# DAC_Schematic.net
KiCad netlist of a schematic drawn in Altium Designer
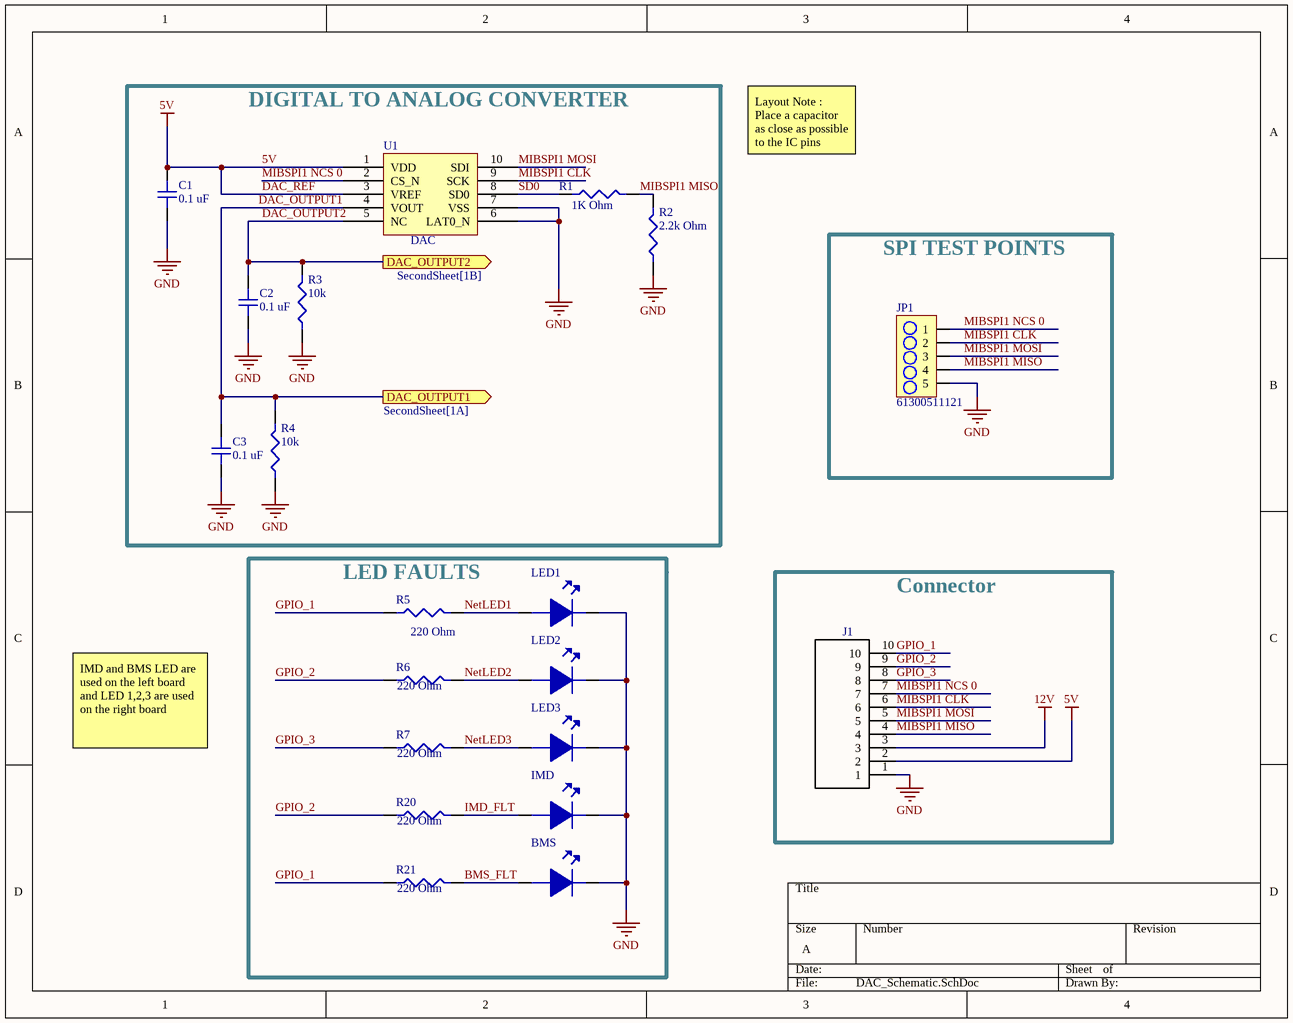
[diagram p0: DAC_Schematic.SchDoc]

(export (version "E")
  (design (tool "Eeschema 10.0.6"))
  (components
    (comp (ref "BMS")
      (value "C503B-RAN-CZ0C0AA1")
      (footprint "Diode")
      (description "LED Uni-Color Red 2-Pin T-1 3/4 Cardboard")
      (fields (field (name "MANUFACTURER") "Cree"))
      (libsource (lib "Dash_Schematic") (part "C503B-RAN-CZ0C0AA1"))
    )
    (comp (ref "C1")
      (value "0.1 uF")
      (footprint "CAPC1608X09N")
      (fields
        (field (name "MANUFACTURER") "KEMET")
        (field (name "MANUFACTURER PART NUMBER") "C0603C104Z3VACTU")
        (field (name "TOLERANCE") "80%")
      )
      (libsource (lib "Dash_Schematic") (part "C0603C104Z3VACTU"))
    )
    (comp (ref "C2")
      (value "0.1 uF")
      (footprint "CAPC1608X09N")
      (fields
        (field (name "MANUFACTURER") "KEMET")
        (field (name "MANUFACTURER PART NUMBER") "C0603C104Z3VACTU")
        (field (name "TOLERANCE") "80%")
      )
      (libsource (lib "Dash_Schematic") (part "C0603C104Z3VACTU"))
    )
    (comp (ref "C3")
      (value "0.1 uF")
      (footprint "CAPC1608X09N")
      (fields
        (field (name "MANUFACTURER") "KEMET")
        (field (name "MANUFACTURER PART NUMBER") "C0603C104Z3VACTU")
        (field (name "TOLERANCE") "80%")
      )
      (libsource (lib "Dash_Schematic") (part "C0603C104Z3VACTU"))
    )
    (comp (ref "IMD")
      (value "C503B-RAN-CZ0C0AA1")
      (footprint "Diode")
      (description "LED Uni-Color Red 2-Pin T-1 3/4 Cardboard")
      (fields (field (name "MANUFACTURER") "Cree"))
      (libsource (lib "Dash_Schematic") (part "C503B-RAN-CZ0C0AA1"))
    )
    (comp (ref "J1")
      (value "103635-9")
      (footprint "*TE_103635-9")
      (description "10 MTE HDR SRRA LATCH .100CL")
      (fields (field (name "DIGI-KEY_PART_NUMBER") "A28643-ND") (field (name "MF") "TE Connectivity"))
      (libsource (lib "103635-9") (part "103635-9"))
    )
    (comp (ref "JP1")
      (value "61300511121")
      (footprint "5PIN_HEADER")
      (fields (field (name "MANUFACTURER") "Wurth Electronics"))
      (libsource (lib "Dash_Schematic") (part "61300511121"))
    )
    (comp (ref "LED1")
      (value "C503B-RAN-CZ0C0AA1")
      (footprint "Diode")
      (description "LED Uni-Color Red 2-Pin T-1 3/4 Cardboard")
      (fields (field (name "MANUFACTURER") "Cree"))
      (libsource (lib "Dash_Schematic") (part "C503B-RAN-CZ0C0AA1"))
    )
    (comp (ref "LED2")
      (value "C503B-RAN-CZ0C0AA1")
      (footprint "Diode")
      (description "LED Uni-Color Red 2-Pin T-1 3/4 Cardboard")
      (fields (field (name "MANUFACTURER") "Cree"))
      (libsource (lib "Dash_Schematic") (part "C503B-RAN-CZ0C0AA1"))
    )
    (comp (ref "LED3")
      (value "C503B-RAN-CZ0C0AA1")
      (footprint "Diode")
      (description "LED Uni-Color Red 2-Pin T-1 3/4 Cardboard")
      (fields (field (name "MANUFACTURER") "Cree"))
      (libsource (lib "Dash_Schematic") (part "C503B-RAN-CZ0C0AA1"))
    )
    (comp (ref "R1")
      (value "1K Ohm")
      (footprint "RESC2012X06N")
      (description "RES SMD 1K OHM 5% 1/8W 0805")
      (fields
        (field (name "MANUFACTURER") "Yageo")
        (field (name "MANUFACTURER PART NUMBER") "RC0805JR-071KL")
      )
      (libsource (lib "Dash_Schematic") (part "RC0805JR-071KL"))
    )
    (comp (ref "R2")
      (value "2.2k Ohm")
      (footprint "RESC2012X06N")
      (description "RES SMD 2.2K OHM 1% 1/8W 0805")
      (fields
        (field (name "MANUFACTURER") "Yageo")
        (field (name "MANUFACTURER PART NUMBER") "RC0805FR-072K2L")
      )
      (libsource (lib "Dash_Schematic") (part "RC0805FR-072K2L"))
    )
    (comp (ref "R3")
      (value "10k")
      (footprint "RESC2012X06N")
      (description "RES 10K OHM 1% 1/4W 0805")
      (fields
        (field (name "MANUFACTURER") "Stackpole Electronics")
        (field (name "MANUFACTURER PART NUMBER") "RNCP0805FTD10K0")
      )
      (libsource (lib "Dash_Schematic") (part "RNCP0805FTD10K0"))
    )
    (comp (ref "R4")
      (value "10k")
      (footprint "RESC2012X06N")
      (description "RES 10K OHM 1% 1/4W 0805")
      (fields
        (field (name "MANUFACTURER") "Stackpole Electronics")
        (field (name "MANUFACTURER PART NUMBER") "RNCP0805FTD10K0")
      )
      (libsource (lib "Dash_Schematic") (part "RNCP0805FTD10K0"))
    )
    (comp (ref "R5")
      (value "220 Ohm")
      (footprint "RESC2012X06N")
      (description "TE CONNECTIVITY - CRGCQ0805F220R - RES, 220R, 1%, 0805, THICK FILM")
      (fields
        (field (name "MANUFACTURER") "TE Connectivity")
        (field (name "MANUFACTURER PART NUMBER") "CRGCQ0805F220R")
      )
      (libsource (lib "Dash_Schematic") (part "CRGCQ0805F220R"))
    )
    (comp (ref "R6")
      (value "220 Ohm")
      (footprint "RESC2012X06N")
      (description "TE CONNECTIVITY - CRGCQ0805F220R - RES, 220R, 1%, 0805, THICK FILM")
      (fields
        (field (name "MANUFACTURER") "TE Connectivity")
        (field (name "MANUFACTURER PART NUMBER") "CRGCQ0805F220R")
      )
      (libsource (lib "Dash_Schematic") (part "CRGCQ0805F220R"))
    )
    (comp (ref "R7")
      (value "220 Ohm")
      (footprint "RESC2012X06N")
      (description "TE CONNECTIVITY - CRGCQ0805F220R - RES, 220R, 1%, 0805, THICK FILM")
      (fields
        (field (name "MANUFACTURER") "TE Connectivity")
        (field (name "MANUFACTURER PART NUMBER") "CRGCQ0805F220R")
      )
      (libsource (lib "Dash_Schematic") (part "CRGCQ0805F220R"))
    )
    (comp (ref "R20")
      (value "220 Ohm")
      (footprint "RESC2012X06N")
      (description "TE CONNECTIVITY - CRGCQ0805F220R - RES, 220R, 1%, 0805, THICK FILM")
      (fields
        (field (name "MANUFACTURER") "TE Connectivity")
        (field (name "MANUFACTURER PART NUMBER") "CRGCQ0805F220R")
      )
      (libsource (lib "Dash_Schematic") (part "CRGCQ0805F220R"))
    )
    (comp (ref "R21")
      (value "220 Ohm")
      (footprint "RESC2012X06N")
      (description "TE CONNECTIVITY - CRGCQ0805F220R - RES, 220R, 1%, 0805, THICK FILM")
      (fields
        (field (name "MANUFACTURER") "TE Connectivity")
        (field (name "MANUFACTURER PART NUMBER") "CRGCQ0805F220R")
      )
      (libsource (lib "Dash_Schematic") (part "CRGCQ0805F220R"))
    )
    (comp (ref "U1")
      (value "DAC")
      (footprint "TSSOP50P490X110-10N")
      (description "MICROCHIP - MCP48FVB02-E/UN - DAC, 8BIT, DUAL, MSOP-10")
      (fields
        (field (name "MANUFACTURER") "Microchip")
        (field (name "MANUFACTURER PART NUMBER") "MCP48FVB02-E/UN")
      )
      (libsource (lib "Dash_Schematic") (part "MCP48FVB02-E/UN"))
    )
  )
  (nets
    (net (code "1") (name "/BMS_FLT") (class "Default")
      (node (ref "BMS") (pin "K") (pinfunction "K_K") (pintype "passive"))
      (node (ref "R21") (pin "2") (pinfunction "2_2") (pintype "passive"))
    )
    (net (code "2") (name "/DAC_OUTPUT1") (class "Default")
      (node (ref "C3") (pin "2") (pinfunction "2_2") (pintype "passive"))
      (node (ref "R4") (pin "2") (pinfunction "2_2") (pintype "passive"))
      (node (ref "U1") (pin "4") (pinfunction "VOUT_4") (pintype "passive"))
    )
    (net (code "3") (name "/DAC_OUTPUT2") (class "Default")
      (node (ref "C2") (pin "2") (pinfunction "2_2") (pintype "passive"))
      (node (ref "R3") (pin "2") (pinfunction "2_2") (pintype "passive"))
      (node (ref "U1") (pin "5") (pinfunction "NC_5") (pintype "passive"))
    )
    (net (code "4") (name "/GPIO_1") (class "Default")
      (node (ref "J1") (pin "10") (pinfunction "10_10") (pintype "passive"))
      (node (ref "R21") (pin "1") (pinfunction "1_1") (pintype "passive"))
      (node (ref "R5") (pin "1") (pinfunction "1_1") (pintype "passive"))
    )
    (net (code "5") (name "/GPIO_2") (class "Default")
      (node (ref "J1") (pin "9") (pinfunction "9_9") (pintype "passive"))
      (node (ref "R20") (pin "1") (pinfunction "1_1") (pintype "passive"))
      (node (ref "R6") (pin "1") (pinfunction "1_1") (pintype "passive"))
    )
    (net (code "6") (name "/GPIO_3") (class "Default")
      (node (ref "J1") (pin "8") (pinfunction "8_8") (pintype "passive"))
      (node (ref "R7") (pin "1") (pinfunction "1_1") (pintype "passive"))
    )
    (net (code "7") (name "/IMD_FLT") (class "Default")
      (node (ref "IMD") (pin "K") (pinfunction "K_K") (pintype "passive"))
      (node (ref "R20") (pin "2") (pinfunction "2_2") (pintype "passive"))
    )
    (net (code "8") (name "/MIBSPI1 CLK") (class "Default")
      (node (ref "J1") (pin "6") (pinfunction "6_6") (pintype "passive"))
      (node (ref "JP1") (pin "2") (pinfunction "2_2") (pintype "passive"))
      (node (ref "U1") (pin "9") (pinfunction "SCK_9") (pintype "passive"))
    )
    (net (code "9") (name "/MIBSPI1 MISO") (class "Default")
      (node (ref "J1") (pin "4") (pinfunction "4_4") (pintype "passive"))
      (node (ref "JP1") (pin "4") (pinfunction "4_4") (pintype "passive"))
      (node (ref "R1") (pin "2") (pinfunction "2_2") (pintype "passive"))
      (node (ref "R2") (pin "2") (pinfunction "2_2") (pintype "passive"))
    )
    (net (code "10") (name "/MIBSPI1 MOSI") (class "Default")
      (node (ref "J1") (pin "5") (pinfunction "5_5") (pintype "passive"))
      (node (ref "JP1") (pin "3") (pinfunction "3_3") (pintype "passive"))
      (node (ref "U1") (pin "10") (pinfunction "SDI_10") (pintype "passive"))
    )
    (net (code "11") (name "/MIBSPI1 NCS 0") (class "Default")
      (node (ref "J1") (pin "7") (pinfunction "7_7") (pintype "passive"))
      (node (ref "JP1") (pin "1") (pinfunction "1_1") (pintype "passive"))
      (node (ref "U1") (pin "2") (pinfunction "CS_N_2") (pintype "passive"))
    )
    (net (code "12") (name "/NetLED1") (class "Default")
      (node (ref "LED1") (pin "K") (pinfunction "K_K") (pintype "passive"))
      (node (ref "R5") (pin "2") (pinfunction "2_2") (pintype "passive"))
    )
    (net (code "13") (name "/NetLED2") (class "Default")
      (node (ref "LED2") (pin "K") (pinfunction "K_K") (pintype "passive"))
      (node (ref "R6") (pin "2") (pinfunction "2_2") (pintype "passive"))
    )
    (net (code "14") (name "/NetLED3") (class "Default")
      (node (ref "LED3") (pin "K") (pinfunction "K_K") (pintype "passive"))
      (node (ref "R7") (pin "2") (pinfunction "2_2") (pintype "passive"))
    )
    (net (code "15") (name "/SD0") (class "Default")
      (node (ref "R1") (pin "1") (pinfunction "1_1") (pintype "passive"))
      (node (ref "U1") (pin "8") (pinfunction "SD0_8") (pintype "passive"))
    )
    (net (code "16") (name "5V") (class "Default")
      (node (ref "C1") (pin "2") (pinfunction "2_2") (pintype "passive"))
      (node (ref "J1") (pin "2") (pinfunction "2_2") (pintype "passive"))
      (node (ref "U1") (pin "1") (pinfunction "VDD_1") (pintype "passive"))
      (node (ref "U1") (pin "3") (pinfunction "VREF_3") (pintype "passive"))
    )
    (net (code "17") (name "12V") (class "Default")
      (node (ref "J1") (pin "3") (pinfunction "3_3") (pintype "passive"))
    )
    (net (code "18") (name "GND") (class "Default")
      (node (ref "BMS") (pin "A") (pinfunction "A_A") (pintype "passive"))
      (node (ref "C1") (pin "1") (pinfunction "1_1") (pintype "passive"))
      (node (ref "C2") (pin "1") (pinfunction "1_1") (pintype "passive"))
      (node (ref "C3") (pin "1") (pinfunction "1_1") (pintype "passive"))
      (node (ref "IMD") (pin "A") (pinfunction "A_A") (pintype "passive"))
      (node (ref "J1") (pin "1") (pinfunction "1_1") (pintype "passive"))
      (node (ref "JP1") (pin "5") (pinfunction "5_5") (pintype "passive"))
      (node (ref "LED1") (pin "A") (pinfunction "A_A") (pintype "passive"))
      (node (ref "LED2") (pin "A") (pinfunction "A_A") (pintype "passive"))
      (node (ref "LED3") (pin "A") (pinfunction "A_A") (pintype "passive"))
      (node (ref "R2") (pin "1") (pinfunction "1_1") (pintype "passive"))
      (node (ref "R3") (pin "1") (pinfunction "1_1") (pintype "passive"))
      (node (ref "R4") (pin "1") (pinfunction "1_1") (pintype "passive"))
      (node (ref "U1") (pin "6") (pinfunction "LAT0_N_6") (pintype "passive"))
      (node (ref "U1") (pin "7") (pinfunction "VSS_7") (pintype "passive"))
    )
  )
)
